# 464421_22-01_RF_Interface.net
KiCad netlist of a schematic drawn in Altium Designer
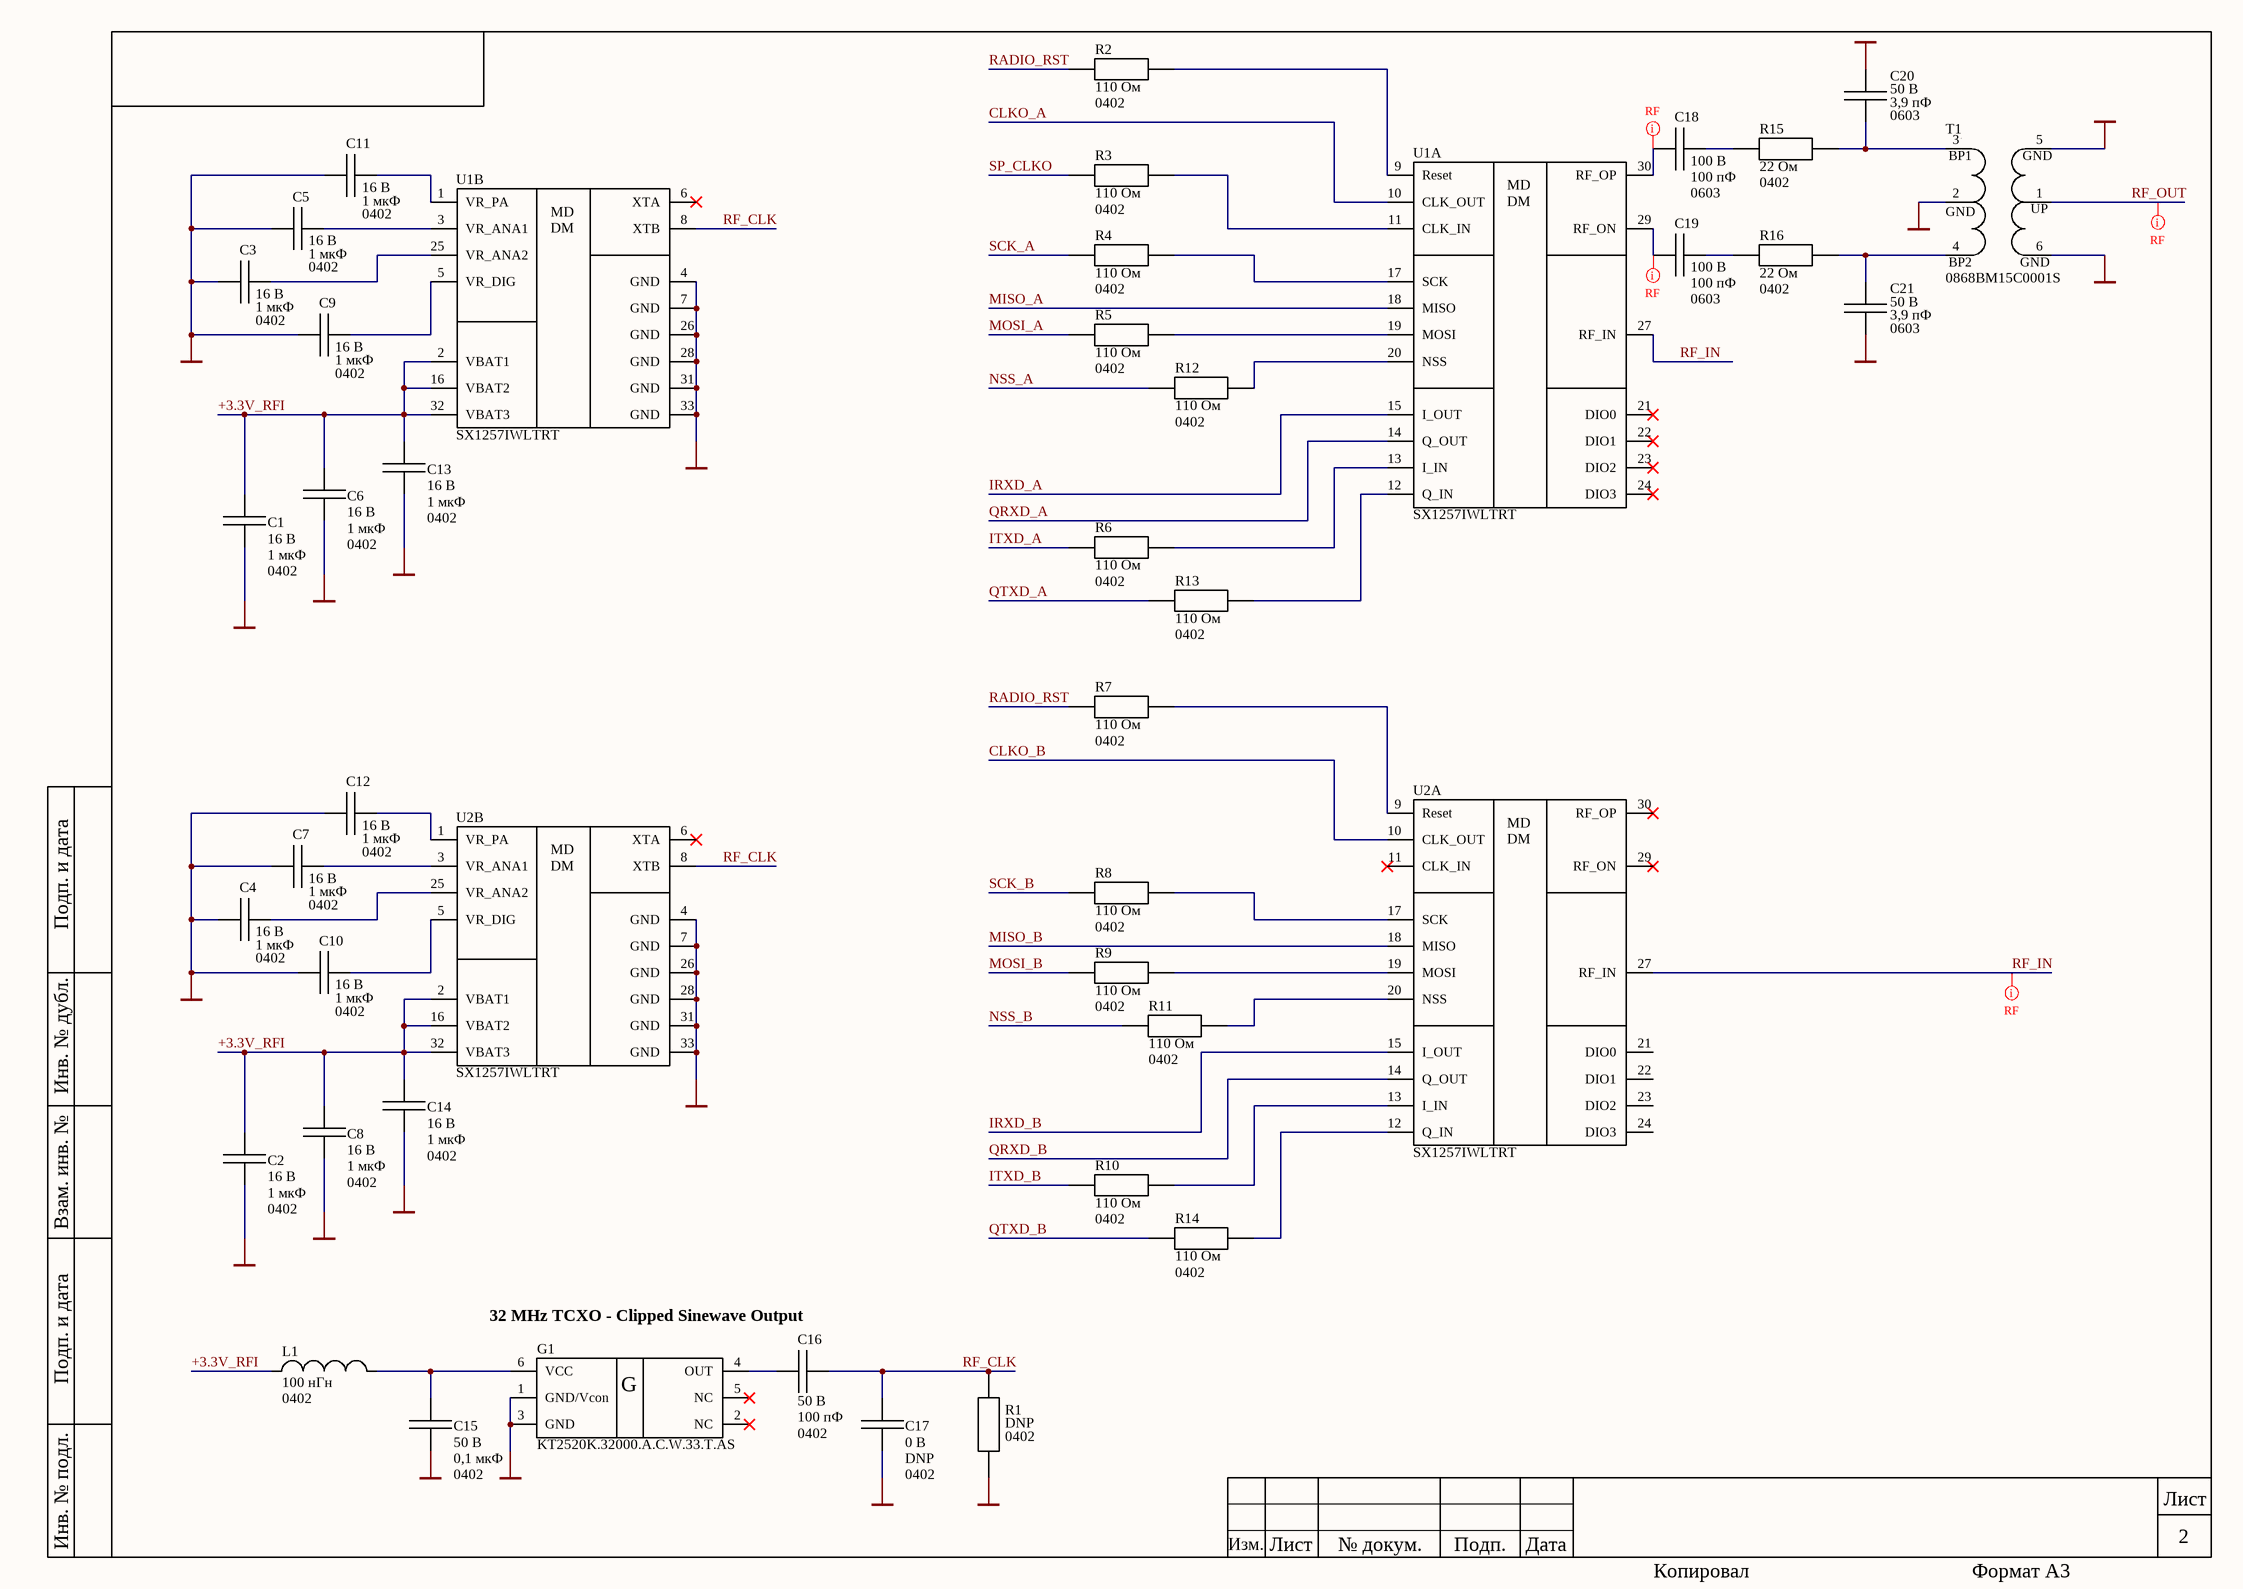
[diagram p0: МПСУ.464421.22-01 RF Interface.SchDoc]

(export (version "E")
  (design (tool "Eeschema 10.0.6"))
  (components
    (comp (ref "C1")
      (value "1 мкФ")
      (footprint "Passive_V2_0:CAPC100X50X55L20N")
      (description "Capacitor 0402")
      (fields
        (field (name "PARTNUMBER") "GRM155R61C105KA12D")
        (field (name "MANUFACTURER") "Murata")
        (field (name "PEAK_CONDITION") "16 В")
        (field (name "PACKAGE") "0402")
        (field (name "DESIGNER") "Свидерский")
      )
      (libsource (lib "Passive_V2_0") (part "C 0402"))
    )
    (comp (ref "C2")
      (value "1 мкФ")
      (footprint "Passive_V2_0:CAPC100X50X55L20N")
      (description "Capacitor 0402")
      (fields
        (field (name "PARTNUMBER") "GRM155R61C105KA12D")
        (field (name "MANUFACTURER") "Murata")
        (field (name "PEAK_CONDITION") "16 В")
        (field (name "PACKAGE") "0402")
        (field (name "DESIGNER") "Свидерский")
      )
      (libsource (lib "Passive_V2_0") (part "C 0402"))
    )
    (comp (ref "C3")
      (value "1 мкФ")
      (footprint "Passive_V2_0:CAPC100X50X55L20N")
      (description "Capacitor 0402")
      (fields
        (field (name "PARTNUMBER") "GRM155R61C105KA12D")
        (field (name "MANUFACTURER") "Murata")
        (field (name "PEAK_CONDITION") "16 В")
        (field (name "PACKAGE") "0402")
        (field (name "DESIGNER") "Свидерский")
      )
      (libsource (lib "Passive_V2_0") (part "C 0402"))
    )
    (comp (ref "C4")
      (value "1 мкФ")
      (footprint "Passive_V2_0:CAPC100X50X55L20N")
      (description "Capacitor 0402")
      (fields
        (field (name "PARTNUMBER") "GRM155R61C105KA12D")
        (field (name "MANUFACTURER") "Murata")
        (field (name "PEAK_CONDITION") "16 В")
        (field (name "PACKAGE") "0402")
        (field (name "DESIGNER") "Свидерский")
      )
      (libsource (lib "Passive_V2_0") (part "C 0402"))
    )
    (comp (ref "C5")
      (value "1 мкФ")
      (footprint "Passive_V2_0:CAPC100X50X55L20N")
      (description "Capacitor 0402")
      (fields
        (field (name "PARTNUMBER") "GRM155R61C105KA12D")
        (field (name "MANUFACTURER") "Murata")
        (field (name "PEAK_CONDITION") "16 В")
        (field (name "PACKAGE") "0402")
        (field (name "DESIGNER") "Свидерский")
      )
      (libsource (lib "Passive_V2_0") (part "C 0402"))
    )
    (comp (ref "C6")
      (value "1 мкФ")
      (footprint "Passive_V2_0:CAPC100X50X55L20N")
      (description "Capacitor 0402")
      (fields
        (field (name "PARTNUMBER") "GRM155R61C105KA12D")
        (field (name "MANUFACTURER") "Murata")
        (field (name "PEAK_CONDITION") "16 В")
        (field (name "PACKAGE") "0402")
        (field (name "DESIGNER") "Свидерский")
      )
      (libsource (lib "Passive_V2_0") (part "C 0402"))
    )
    (comp (ref "C7")
      (value "1 мкФ")
      (footprint "Passive_V2_0:CAPC100X50X55L20N")
      (description "Capacitor 0402")
      (fields
        (field (name "PARTNUMBER") "GRM155R61C105KA12D")
        (field (name "MANUFACTURER") "Murata")
        (field (name "PEAK_CONDITION") "16 В")
        (field (name "PACKAGE") "0402")
        (field (name "DESIGNER") "Свидерский")
      )
      (libsource (lib "Passive_V2_0") (part "C 0402"))
    )
    (comp (ref "C8")
      (value "1 мкФ")
      (footprint "Passive_V2_0:CAPC100X50X55L20N")
      (description "Capacitor 0402")
      (fields
        (field (name "PARTNUMBER") "GRM155R61C105KA12D")
        (field (name "MANUFACTURER") "Murata")
        (field (name "PEAK_CONDITION") "16 В")
        (field (name "PACKAGE") "0402")
        (field (name "DESIGNER") "Свидерский")
      )
      (libsource (lib "Passive_V2_0") (part "C 0402"))
    )
    (comp (ref "C9")
      (value "1 мкФ")
      (footprint "Passive_V2_0:CAPC100X50X55L20N")
      (description "Capacitor 0402")
      (fields
        (field (name "PARTNUMBER") "GRM155R61C105KA12D")
        (field (name "MANUFACTURER") "Murata")
        (field (name "PEAK_CONDITION") "16 В")
        (field (name "PACKAGE") "0402")
        (field (name "DESIGNER") "Свидерский")
      )
      (libsource (lib "Passive_V2_0") (part "C 0402"))
    )
    (comp (ref "C10")
      (value "1 мкФ")
      (footprint "Passive_V2_0:CAPC100X50X55L20N")
      (description "Capacitor 0402")
      (fields
        (field (name "PARTNUMBER") "GRM155R61C105KA12D")
        (field (name "MANUFACTURER") "Murata")
        (field (name "PEAK_CONDITION") "16 В")
        (field (name "PACKAGE") "0402")
        (field (name "DESIGNER") "Свидерский")
      )
      (libsource (lib "Passive_V2_0") (part "C 0402"))
    )
    (comp (ref "C11")
      (value "1 мкФ")
      (footprint "Passive_V2_0:CAPC100X50X55L20N")
      (description "Capacitor 0402")
      (fields
        (field (name "PARTNUMBER") "GRM155R61C105KA12D")
        (field (name "MANUFACTURER") "Murata")
        (field (name "PEAK_CONDITION") "16 В")
        (field (name "PACKAGE") "0402")
        (field (name "DESIGNER") "Свидерский")
      )
      (libsource (lib "Passive_V2_0") (part "C 0402"))
    )
    (comp (ref "C12")
      (value "1 мкФ")
      (footprint "Passive_V2_0:CAPC100X50X55L20N")
      (description "Capacitor 0402")
      (fields
        (field (name "PARTNUMBER") "GRM155R61C105KA12D")
        (field (name "MANUFACTURER") "Murata")
        (field (name "PEAK_CONDITION") "16 В")
        (field (name "PACKAGE") "0402")
        (field (name "DESIGNER") "Свидерский")
      )
      (libsource (lib "Passive_V2_0") (part "C 0402"))
    )
    (comp (ref "C13")
      (value "1 мкФ")
      (footprint "Passive_V2_0:CAPC100X50X55L20N")
      (description "Capacitor 0402")
      (fields
        (field (name "PARTNUMBER") "GRM155R61C105KA12D")
        (field (name "MANUFACTURER") "Murata")
        (field (name "PEAK_CONDITION") "16 В")
        (field (name "PACKAGE") "0402")
        (field (name "DESIGNER") "Свидерский")
      )
      (libsource (lib "Passive_V2_0") (part "C 0402"))
    )
    (comp (ref "C14")
      (value "1 мкФ")
      (footprint "Passive_V2_0:CAPC100X50X55L20N")
      (description "Capacitor 0402")
      (fields
        (field (name "PARTNUMBER") "GRM155R61C105KA12D")
        (field (name "MANUFACTURER") "Murata")
        (field (name "PEAK_CONDITION") "16 В")
        (field (name "PACKAGE") "0402")
        (field (name "DESIGNER") "Свидерский")
      )
      (libsource (lib "Passive_V2_0") (part "C 0402"))
    )
    (comp (ref "C15")
      (value "0,1 мкФ")
      (footprint "Passive_V2_0:CAPC100X50X55L20N")
      (description "Capacitor 0402")
      (fields
        (field (name "PARTNUMBER") "GRM155R71H104KE14J")
        (field (name "MANUFACTURER") "Murata")
        (field (name "PEAK_CONDITION") "50 В")
        (field (name "PACKAGE") "0402")
        (field (name "DESIGNER") "Свидерский")
      )
      (libsource (lib "Passive_V2_0") (part "C 0402"))
    )
    (comp (ref "C16")
      (value "100 пФ")
      (footprint "Passive_V2_0:CAPC100X50X55L20N")
      (description "Capacitor 0402")
      (fields
        (field (name "PARTNUMBER") "GRM1555C1H101JZ01D")
        (field (name "MANUFACTURER") "Murata")
        (field (name "PEAK_CONDITION") "50 В")
        (field (name "PACKAGE") "0402")
        (field (name "DESIGNER") "Свидерский")
      )
      (libsource (lib "Passive_V2_0") (part "C 0402"))
    )
    (comp (ref "C17")
      (value "DNP")
      (footprint "Passive_V2_0:CAPC100X50X55L20N")
      (description "Capacitor 0402")
      (fields
        (field (name "TOLERANCE") "0 %")
        (field (name "PEAK_CONDITION") "0 В")
        (field (name "PACKAGE") "0402")
        (field (name "Comment") "DNP 0402")
        (field (name "DESIGNER") "Свидерский")
      )
      (libsource (lib "Passive_V2_0") (part "C 0402"))
    )
    (comp (ref "C18")
      (value "100 пФ")
      (footprint "Passive_V2_0:CAPC160X80X90L30N")
      (description "Capacitor 0603")
      (fields
        (field (name "PARTNUMBER") "GRM1885C2A101FA01D")
        (field (name "MANUFACTURER") "Murata")
        (field (name "PEAK_CONDITION") "100 В")
        (field (name "PACKAGE") "0603")
        (field (name "DESIGNER") "Свидерский")
      )
      (libsource (lib "Passive_V2_0") (part "C 0603"))
    )
    (comp (ref "C19")
      (value "100 пФ")
      (footprint "Passive_V2_0:CAPC160X80X90L30N")
      (description "Capacitor 0603")
      (fields
        (field (name "PARTNUMBER") "GRM1885C2A101FA01D")
        (field (name "MANUFACTURER") "Murata")
        (field (name "PEAK_CONDITION") "100 В")
        (field (name "PACKAGE") "0603")
        (field (name "DESIGNER") "Свидерский")
      )
      (libsource (lib "Passive_V2_0") (part "C 0603"))
    )
    (comp (ref "C20")
      (value "3,9 пФ")
      (footprint "Passive_V2_0:CAPC160X80X90L30N")
      (description "Capacitor 0603")
      (fields
        (field (name "PARTNUMBER") "GRM1885C1H3R9CZ01D")
        (field (name "MANUFACTURER") "Murata")
        (field (name "PEAK_CONDITION") "50 В")
        (field (name "PACKAGE") "0603")
        (field (name "DESIGNER") "Свидерский")
      )
      (libsource (lib "Passive_V2_0") (part "C 0603"))
    )
    (comp (ref "C21")
      (value "3,9 пФ")
      (footprint "Passive_V2_0:CAPC160X80X90L30N")
      (description "Capacitor 0603")
      (fields
        (field (name "PARTNUMBER") "GRM1885C1H3R9CZ01D")
        (field (name "MANUFACTURER") "Murata")
        (field (name "PEAK_CONDITION") "50 В")
        (field (name "PACKAGE") "0603")
        (field (name "DESIGNER") "Свидерский")
      )
      (libsource (lib "Passive_V2_0") (part "C 0603"))
    )
    (comp (ref "G1")
      (value "KT2520K.32000.A.C.W.33.T.AS")
      (footprint "IC_V2_0:KT2520K")
      (description "Temperature Compensated Crystal Oscillators (TCXO, VCTCXO) Surface Mount Type")
      (fields
        (field (name "MANUFACTURER") "Kyocera")
        (field (name "PARTNUMBER") "KT2520K.32000.A.C.W.33.T.AS")
        (field (name "DESIGNER") "Лазба")
      )
      (libsource (lib "IC_V2_0") (part "KT2520K.*****.*.*.*.**.*.*"))
    )
    (comp (ref "L1")
      (value "100 нГн")
      (footprint "Passive_V2_0:INDC100X50X60L10N")
      (description "Inductor 0402")
      (fields
        (field (name "PARTNUMBER") "LQG15HNR10J02D")
        (field (name "TOLERANCE") "5 %")
        (field (name "PACKAGE") "0402")
        (field (name "DESIGNER") "Свидерский")
      )
      (libsource (lib "Passive_V2_0") (part "L 0402"))
    )
    (comp (ref "R1")
      (value "DNP")
      (footprint "Passive_V2_0:RESC100X50X40L25N")
      (description "Resistor 0402")
      (fields
        (field (name "TOLERANCE") "0 %")
        (field (name "PACKAGE") "0402")
        (field (name "Comment") "DNP 0402")
        (field (name "DESIGNER") "Свидерский")
      )
      (libsource (lib "") (part "R 0402_1"))
    )
    (comp (ref "R2")
      (value "110 Ом")
      (footprint "Passive_V2_0:RESC100X50X40L25N")
      (description "Resistor 0402")
      (fields
        (field (name "PARTNUMBER") "RC-02U111JT")
        (field (name "TOLERANCE") "5 %")
        (field (name "PACKAGE") "0402")
        (field (name "DESIGNER") "Свидерский")
      )
      (libsource (lib "Passive_V2_0") (part "R 0402"))
    )
    (comp (ref "R3")
      (value "110 Ом")
      (footprint "Passive_V2_0:RESC100X50X40L25N")
      (description "Resistor 0402")
      (fields
        (field (name "PARTNUMBER") "RC-02U111JT")
        (field (name "TOLERANCE") "5 %")
        (field (name "PACKAGE") "0402")
        (field (name "DESIGNER") "Свидерский")
      )
      (libsource (lib "Passive_V2_0") (part "R 0402"))
    )
    (comp (ref "R4")
      (value "110 Ом")
      (footprint "Passive_V2_0:RESC100X50X40L25N")
      (description "Resistor 0402")
      (fields
        (field (name "PARTNUMBER") "RC-02U111JT")
        (field (name "TOLERANCE") "5 %")
        (field (name "PACKAGE") "0402")
        (field (name "DESIGNER") "Свидерский")
      )
      (libsource (lib "Passive_V2_0") (part "R 0402"))
    )
    (comp (ref "R5")
      (value "110 Ом")
      (footprint "Passive_V2_0:RESC100X50X40L25N")
      (description "Resistor 0402")
      (fields
        (field (name "PARTNUMBER") "RC-02U111JT")
        (field (name "TOLERANCE") "5 %")
        (field (name "PACKAGE") "0402")
        (field (name "DESIGNER") "Свидерский")
      )
      (libsource (lib "Passive_V2_0") (part "R 0402"))
    )
    (comp (ref "R6")
      (value "110 Ом")
      (footprint "Passive_V2_0:RESC100X50X40L25N")
      (description "Resistor 0402")
      (fields
        (field (name "PARTNUMBER") "RC-02U111JT")
        (field (name "TOLERANCE") "5 %")
        (field (name "PACKAGE") "0402")
        (field (name "DESIGNER") "Свидерский")
      )
      (libsource (lib "Passive_V2_0") (part "R 0402"))
    )
    (comp (ref "R7")
      (value "110 Ом")
      (footprint "Passive_V2_0:RESC100X50X40L25N")
      (description "Resistor 0402")
      (fields
        (field (name "PARTNUMBER") "RC-02U111JT")
        (field (name "TOLERANCE") "5 %")
        (field (name "PACKAGE") "0402")
        (field (name "DESIGNER") "Свидерский")
      )
      (libsource (lib "Passive_V2_0") (part "R 0402"))
    )
    (comp (ref "R8")
      (value "110 Ом")
      (footprint "Passive_V2_0:RESC100X50X40L25N")
      (description "Resistor 0402")
      (fields
        (field (name "PARTNUMBER") "RC-02U111JT")
        (field (name "TOLERANCE") "5 %")
        (field (name "PACKAGE") "0402")
        (field (name "DESIGNER") "Свидерский")
      )
      (libsource (lib "Passive_V2_0") (part "R 0402"))
    )
    (comp (ref "R9")
      (value "110 Ом")
      (footprint "Passive_V2_0:RESC100X50X40L25N")
      (description "Resistor 0402")
      (fields
        (field (name "PARTNUMBER") "RC-02U111JT")
        (field (name "TOLERANCE") "5 %")
        (field (name "PACKAGE") "0402")
        (field (name "DESIGNER") "Свидерский")
      )
      (libsource (lib "Passive_V2_0") (part "R 0402"))
    )
    (comp (ref "R10")
      (value "110 Ом")
      (footprint "Passive_V2_0:RESC100X50X40L25N")
      (description "Resistor 0402")
      (fields
        (field (name "PARTNUMBER") "RC-02U111JT")
        (field (name "TOLERANCE") "5 %")
        (field (name "PACKAGE") "0402")
        (field (name "DESIGNER") "Свидерский")
      )
      (libsource (lib "Passive_V2_0") (part "R 0402"))
    )
    (comp (ref "R11")
      (value "110 Ом")
      (footprint "Passive_V2_0:RESC100X50X40L25N")
      (description "Resistor 0402")
      (fields
        (field (name "PARTNUMBER") "RC-02U111JT")
        (field (name "TOLERANCE") "5 %")
        (field (name "PACKAGE") "0402")
        (field (name "DESIGNER") "Свидерский")
      )
      (libsource (lib "Passive_V2_0") (part "R 0402"))
    )
    (comp (ref "R12")
      (value "110 Ом")
      (footprint "Passive_V2_0:RESC100X50X40L25N")
      (description "Resistor 0402")
      (fields
        (field (name "PARTNUMBER") "RC-02U111JT")
        (field (name "TOLERANCE") "5 %")
        (field (name "PACKAGE") "0402")
        (field (name "DESIGNER") "Свидерский")
      )
      (libsource (lib "Passive_V2_0") (part "R 0402"))
    )
    (comp (ref "R13")
      (value "110 Ом")
      (footprint "Passive_V2_0:RESC100X50X40L25N")
      (description "Resistor 0402")
      (fields
        (field (name "PARTNUMBER") "RC-02U111JT")
        (field (name "TOLERANCE") "5 %")
        (field (name "PACKAGE") "0402")
        (field (name "DESIGNER") "Свидерский")
      )
      (libsource (lib "Passive_V2_0") (part "R 0402"))
    )
    (comp (ref "R14")
      (value "110 Ом")
      (footprint "Passive_V2_0:RESC100X50X40L25N")
      (description "Resistor 0402")
      (fields
        (field (name "PARTNUMBER") "RC-02U111JT")
        (field (name "TOLERANCE") "5 %")
        (field (name "PACKAGE") "0402")
        (field (name "DESIGNER") "Свидерский")
      )
      (libsource (lib "Passive_V2_0") (part "R 0402"))
    )
    (comp (ref "R15")
      (value "22 Ом")
      (footprint "Passive_V2_0:RESC100X50X40L25N")
      (description "Resistor 0402")
      (fields
        (field (name "PARTNUMBER") "RC0402FR-0722RL")
        (field (name "TOLERANCE") "1 %")
        (field (name "PACKAGE") "0402")
        (field (name "DESIGNER") "Свидерский")
      )
      (libsource (lib "Passive_V2_0") (part "R 0402"))
    )
    (comp (ref "R16")
      (value "22 Ом")
      (footprint "Passive_V2_0:RESC100X50X40L25N")
      (description "Resistor 0402")
      (fields
        (field (name "PARTNUMBER") "RC0402FR-0722RL")
        (field (name "TOLERANCE") "1 %")
        (field (name "PACKAGE") "0402")
        (field (name "DESIGNER") "Свидерский")
      )
      (libsource (lib "Passive_V2_0") (part "R 0402"))
    )
    (comp (ref "T1")
      (value "0868BM15C0001S")
      (footprint "Passive_V2_0:LCC065P125X200X085-6")
      (fields
        (field (name "MANUFACTURER") "Johanson Technology Inc.")
        (field (name "PARTNUMBER") "0868BM15C0001S")
        (field (name "DESIGNER") "Лазба")
      )
      (libsource (lib "Passive_V2_0") (part "0868BM15C0001*"))
    )
    (comp (ref "U1")
      (value "SX1257IWLTRT")
      (footprint "IC_V2_0:SX1257IWLTRT")
      (description "LoRa Core™ Low Power Digital I and Q RF Multi-PHY Mode Analog Front End 860-1000MHz")
      (fields
        (field (name "MANUFACTURER") "Semtech")
        (field (name "PARTNUMBER") "SX1257IWLTRT")
        (field (name "DESIGNER") "Лазба")
      )
      (libsource (lib "IC_V2_0") (part "SX1257IWLTRT"))
    )
    (comp (ref "U2")
      (value "SX1257IWLTRT")
      (footprint "IC_V2_0:SX1257IWLTRT")
      (description "LoRa Core™ Low Power Digital I and Q RF Multi-PHY Mode Analog Front End 860-1000MHz")
      (fields
        (field (name "MANUFACTURER") "Semtech")
        (field (name "PARTNUMBER") "SX1257IWLTRT")
        (field (name "DESIGNER") "Лазба")
      )
      (libsource (lib "IC_V2_0") (part "SX1257IWLTRT"))
    )
  )
  (nets
    (net (code "1") (name "/+3.3V_RFI") (class "Default")
      (node (ref "C1") (pin "2") (pinfunction "2_2") (pintype "passive"))
      (node (ref "C13") (pin "2") (pinfunction "2_2") (pintype "passive"))
      (node (ref "C14") (pin "2") (pinfunction "2_2") (pintype "passive"))
      (node (ref "C2") (pin "2") (pinfunction "2_2") (pintype "passive"))
      (node (ref "C6") (pin "2") (pinfunction "2_2") (pintype "passive"))
      (node (ref "C8") (pin "2") (pinfunction "2_2") (pintype "passive"))
      (node (ref "L1") (pin "1") (pinfunction "1_1") (pintype "passive"))
      (node (ref "U1") (pin "16") (pinfunction "VBAT2_16") (pintype "passive"))
      (node (ref "U1") (pin "2") (pinfunction "VBAT1_2") (pintype "passive"))
      (node (ref "U1") (pin "32") (pinfunction "VBAT3_32") (pintype "passive"))
      (node (ref "U2") (pin "16") (pinfunction "VBAT2_16") (pintype "passive"))
      (node (ref "U2") (pin "2") (pinfunction "VBAT1_2") (pintype "passive"))
      (node (ref "U2") (pin "32") (pinfunction "VBAT3_32") (pintype "passive"))
    )
    (net (code "2") (name "/CLKO_A") (class "Default")
      (node (ref "U1") (pin "10") (pinfunction "CLK_OUT_10") (pintype "passive"))
    )
    (net (code "3") (name "/CLKO_B") (class "Default")
      (node (ref "U2") (pin "10") (pinfunction "CLK_OUT_10") (pintype "passive"))
    )
    (net (code "4") (name "/IRXD_A") (class "Default")
      (node (ref "U1") (pin "15") (pinfunction "I_OUT_15") (pintype "passive"))
    )
    (net (code "5") (name "/IRXD_B") (class "Default")
      (node (ref "U2") (pin "15") (pinfunction "I_OUT_15") (pintype "passive"))
    )
    (net (code "6") (name "/ITXD_A") (class "Default")
      (node (ref "R6") (pin "1") (pinfunction "1_1") (pintype "passive"))
    )
    (net (code "7") (name "/ITXD_B") (class "Default")
      (node (ref "R10") (pin "1") (pinfunction "1_1") (pintype "passive"))
    )
    (net (code "8") (name "/MISO_A") (class "Default")
      (node (ref "U1") (pin "18") (pinfunction "MISO_18") (pintype "passive"))
    )
    (net (code "9") (name "/MISO_B") (class "Default")
      (node (ref "U2") (pin "18") (pinfunction "MISO_18") (pintype "passive"))
    )
    (net (code "10") (name "/MOSI_A") (class "Default")
      (node (ref "R5") (pin "1") (pinfunction "1_1") (pintype "passive"))
    )
    (net (code "11") (name "/MOSI_B") (class "Default")
      (node (ref "R9") (pin "1") (pinfunction "1_1") (pintype "passive"))
    )
    (net (code "12") (name "/NSS_A") (class "Default")
      (node (ref "R12") (pin "1") (pinfunction "1_1") (pintype "passive"))
    )
    (net (code "13") (name "/NSS_B") (class "Default")
      (node (ref "R11") (pin "1") (pinfunction "1_1") (pintype "passive"))
    )
    (net (code "14") (name "/QRXD_A") (class "Default")
      (node (ref "U1") (pin "14") (pinfunction "Q_OUT_14") (pintype "passive"))
    )
    (net (code "15") (name "/QRXD_B") (class "Default")
      (node (ref "U2") (pin "14") (pinfunction "Q_OUT_14") (pintype "passive"))
    )
    (net (code "16") (name "/QTXD_A") (class "Default")
      (node (ref "R13") (pin "1") (pinfunction "1_1") (pintype "passive"))
    )
    (net (code "17") (name "/QTXD_B") (class "Default")
      (node (ref "R14") (pin "1") (pinfunction "1_1") (pintype "passive"))
    )
    (net (code "18") (name "/RADIO_RST") (class "Default")
      (node (ref "R2") (pin "1") (pinfunction "1_1") (pintype "passive"))
      (node (ref "R7") (pin "1") (pinfunction "1_1") (pintype "passive"))
    )
    (net (code "19") (name "/RF_CLK") (class "Default")
      (node (ref "C16") (pin "2") (pinfunction "2_2") (pintype "passive"))
      (node (ref "C17") (pin "1") (pinfunction "1_1") (pintype "passive"))
      (node (ref "R1") (pin "1") (pinfunction "1_1") (pintype "passive"))
      (node (ref "U1") (pin "8") (pinfunction "XTB_8") (pintype "passive"))
      (node (ref "U2") (pin "8") (pinfunction "XTB_8") (pintype "passive"))
    )
    (net (code "20") (name "/RF_IN") (class "Default")
      (node (ref "U1") (pin "27") (pinfunction "RF_IN_27") (pintype "passive"))
      (node (ref "U2") (pin "27") (pinfunction "RF_IN_27") (pintype "passive"))
    )
    (net (code "21") (name "/RF_OUT") (class "Default")
      (node (ref "T1") (pin "1") (pinfunction "UP_1") (pintype "passive"))
    )
    (net (code "22") (name "/SCK_A") (class "Default")
      (node (ref "R4") (pin "1") (pinfunction "1_1") (pintype "passive"))
    )
    (net (code "23") (name "/SCK_B") (class "Default")
      (node (ref "R8") (pin "1") (pinfunction "1_1") (pintype "passive"))
    )
    (net (code "24") (name "/SP_CLKO") (class "Default")
      (node (ref "R3") (pin "1") (pinfunction "1_1") (pintype "passive"))
    )
    (net (code "25") (name "GND") (class "Default")
      (node (ref "C1") (pin "1") (pinfunction "1_1") (pintype "passive"))
      (node (ref "C10") (pin "2") (pinfunction "2_2") (pintype "passive"))
      (node (ref "C11") (pin "2") (pinfunction "2_2") (pintype "passive"))
      (node (ref "C12") (pin "2") (pinfunction "2_2") (pintype "passive"))
      (node (ref "C13") (pin "1") (pinfunction "1_1") (pintype "passive"))
      (node (ref "C14") (pin "1") (pinfunction "1_1") (pintype "passive"))
      (node (ref "C15") (pin "2") (pinfunction "2_2") (pintype "passive"))
      (node (ref "C17") (pin "2") (pinfunction "2_2") (pintype "passive"))
      (node (ref "C2") (pin "1") (pinfunction "1_1") (pintype "passive"))
      (node (ref "C20") (pin "1") (pinfunction "1_1") (pintype "passive"))
      (node (ref "C21") (pin "2") (pinfunction "2_2") (pintype "passive"))
      (node (ref "C3") (pin "2") (pinfunction "2_2") (pintype "passive"))
      (node (ref "C4") (pin "2") (pinfunction "2_2") (pintype "passive"))
      (node (ref "C5") (pin "2") (pinfunction "2_2") (pintype "passive"))
      (node (ref "C6") (pin "1") (pinfunction "1_1") (pintype "passive"))
      (node (ref "C7") (pin "2") (pinfunction "2_2") (pintype "passive"))
      (node (ref "C8") (pin "1") (pinfunction "1_1") (pintype "passive"))
      (node (ref "C9") (pin "2") (pinfunction "2_2") (pintype "passive"))
      (node (ref "G1") (pin "1") (pinfunction "GND/Vcon_1") (pintype "passive"))
      (node (ref "G1") (pin "3") (pinfunction "GND_3") (pintype "passive"))
      (node (ref "R1") (pin "2") (pinfunction "2_2") (pintype "passive"))
      (node (ref "T1") (pin "2") (pinfunction "GND_2") (pintype "passive"))
      (node (ref "T1") (pin "5") (pinfunction "GND_5") (pintype "passive"))
      (node (ref "T1") (pin "6") (pinfunction "GND_6") (pintype "passive"))
      (node (ref "U1") (pin "26") (pinfunction "GND_26") (pintype "passive"))
      (node (ref "U1") (pin "28") (pinfunction "GND_28") (pintype "passive"))
      (node (ref "U1") (pin "31") (pinfunction "GND_31") (pintype "passive"))
      (node (ref "U1") (pin "33") (pinfunction "GND_33") (pintype "passive"))
      (node (ref "U1") (pin "4") (pinfunction "GND_4") (pintype "passive"))
      (node (ref "U1") (pin "7") (pinfunction "GND_7") (pintype "passive"))
      (node (ref "U2") (pin "26") (pinfunction "GND_26") (pintype "passive"))
      (node (ref "U2") (pin "28") (pinfunction "GND_28") (pintype "passive"))
      (node (ref "U2") (pin "31") (pinfunction "GND_31") (pintype "passive"))
      (node (ref "U2") (pin "33") (pinfunction "GND_33") (pintype "passive"))
      (node (ref "U2") (pin "4") (pinfunction "GND_4") (pintype "passive"))
      (node (ref "U2") (pin "7") (pinfunction "GND_7") (pintype "passive"))
    )
    (net (code "26") (name "Net-(C18-Pad2)") (class "Default")
      (node (ref "C18") (pin "2") (pinfunction "2_2") (pintype "passive"))
      (node (ref "R15") (pin "1") (pinfunction "1_1") (pintype "passive"))
    )
    (net (code "27") (name "Net-(C19-Pad2)") (class "Default")
      (node (ref "C19") (pin "2") (pinfunction "2_2") (pintype "passive"))
      (node (ref "R16") (pin "1") (pinfunction "1_1") (pintype "passive"))
    )
    (net (code "28") (name "Net-(G1-OUT)") (class "Default")
      (node (ref "C16") (pin "1") (pinfunction "1_1") (pintype "passive"))
      (node (ref "G1") (pin "4") (pinfunction "OUT_4") (pintype "passive"))
    )
    (net (code "29") (name "Net-(G1-VCC)") (class "Default")
      (node (ref "C15") (pin "1") (pinfunction "1_1") (pintype "passive"))
      (node (ref "G1") (pin "6") (pinfunction "VCC_6") (pintype "passive"))
      (node (ref "L1") (pin "2") (pinfunction "2_2") (pintype "passive"))
    )
    (net (code "30") (name "Net-(T1-BP1)") (class "Default")
      (node (ref "C20") (pin "2") (pinfunction "2_2") (pintype "passive"))
      (node (ref "R15") (pin "2") (pinfunction "2_2") (pintype "passive"))
      (node (ref "T1") (pin "3") (pinfunction "BP1_3") (pintype "passive"))
    )
    (net (code "31") (name "Net-(T1-BP2)") (class "Default")
      (node (ref "C21") (pin "1") (pinfunction "1_1") (pintype "passive"))
      (node (ref "R16") (pin "2") (pinfunction "2_2") (pintype "passive"))
      (node (ref "T1") (pin "4") (pinfunction "BP2_4") (pintype "passive"))
    )
    (net (code "32") (name "Net-(U1A-CLK_IN)") (class "Default")
      (node (ref "R3") (pin "2") (pinfunction "2_2") (pintype "passive"))
      (node (ref "U1") (pin "11") (pinfunction "CLK_IN_11") (pintype "passive"))
    )
    (net (code "33") (name "Net-(U1A-I_IN)") (class "Default")
      (node (ref "R6") (pin "2") (pinfunction "2_2") (pintype "passive"))
      (node (ref "U1") (pin "13") (pinfunction "I_IN_13") (pintype "passive"))
    )
    (net (code "34") (name "Net-(U1A-MOSI)") (class "Default")
      (node (ref "R5") (pin "2") (pinfunction "2_2") (pintype "passive"))
      (node (ref "U1") (pin "19") (pinfunction "MOSI_19") (pintype "passive"))
    )
    (net (code "35") (name "Net-(U1A-NSS)") (class "Default")
      (node (ref "R12") (pin "2") (pinfunction "2_2") (pintype "passive"))
      (node (ref "U1") (pin "20") (pinfunction "NSS_20") (pintype "passive"))
    )
    (net (code "36") (name "Net-(U1A-Q_IN)") (class "Default")
      (node (ref "R13") (pin "2") (pinfunction "2_2") (pintype "passive"))
      (node (ref "U1") (pin "12") (pinfunction "Q_IN_12") (pintype "passive"))
    )
    (net (code "37") (name "Net-(U1A-RF_ON)") (class "Default")
      (node (ref "C19") (pin "1") (pinfunction "1_1") (pintype "passive"))
      (node (ref "U1") (pin "29") (pinfunction "RF_ON_29") (pintype "passive"))
    )
    (net (code "38") (name "Net-(U1A-RF_OP)") (class "Default")
      (node (ref "C18") (pin "1") (pinfunction "1_1") (pintype "passive"))
      (node (ref "U1") (pin "30") (pinfunction "RF_OP_30") (pintype "passive"))
    )
    (net (code "39") (name "Net-(U1A-Reset)") (class "Default")
      (node (ref "R2") (pin "2") (pinfunction "2_2") (pintype "passive"))
      (node (ref "U1") (pin "9") (pinfunction "Reset_9") (pintype "passive"))
    )
    (net (code "40") (name "Net-(U1A-SCK)") (class "Default")
      (node (ref "R4") (pin "2") (pinfunction "2_2") (pintype "passive"))
      (node (ref "U1") (pin "17") (pinfunction "SCK_17") (pintype "passive"))
    )
    (net (code "41") (name "Net-(U1B-VR_ANA1)") (class "Default")
      (node (ref "C5") (pin "1") (pinfunction "1_1") (pintype "passive"))
      (node (ref "U1") (pin "3") (pinfunction "VR_ANA1_3") (pintype "passive"))
    )
    (net (code "42") (name "Net-(U1B-VR_ANA2)") (class "Default")
      (node (ref "C3") (pin "1") (pinfunction "1_1") (pintype "passive"))
      (node (ref "U1") (pin "25") (pinfunction "VR_ANA2_25") (pintype "passive"))
    )
    (net (code "43") (name "Net-(U1B-VR_DIG)") (class "Default")
      (node (ref "C9") (pin "1") (pinfunction "1_1") (pintype "passive"))
      (node (ref "U1") (pin "5") (pinfunction "VR_DIG_5") (pintype "passive"))
    )
    (net (code "44") (name "Net-(U1B-VR_PA)") (class "Default")
      (node (ref "C11") (pin "1") (pinfunction "1_1") (pintype "passive"))
      (node (ref "U1") (pin "1") (pinfunction "VR_PA_1") (pintype "passive"))
    )
    (net (code "45") (name "Net-(U2A-I_IN)") (class "Default")
      (node (ref "R10") (pin "2") (pinfunction "2_2") (pintype "passive"))
      (node (ref "U2") (pin "13") (pinfunction "I_IN_13") (pintype "passive"))
    )
    (net (code "46") (name "Net-(U2A-MOSI)") (class "Default")
      (node (ref "R9") (pin "2") (pinfunction "2_2") (pintype "passive"))
      (node (ref "U2") (pin "19") (pinfunction "MOSI_19") (pintype "passive"))
    )
    (net (code "47") (name "Net-(U2A-NSS)") (class "Default")
      (node (ref "R11") (pin "2") (pinfunction "2_2") (pintype "passive"))
      (node (ref "U2") (pin "20") (pinfunction "NSS_20") (pintype "passive"))
    )
    (net (code "48") (name "Net-(U2A-Q_IN)") (class "Default")
      (node (ref "R14") (pin "2") (pinfunction "2_2") (pintype "passive"))
      (node (ref "U2") (pin "12") (pinfunction "Q_IN_12") (pintype "passive"))
    )
    (net (code "49") (name "Net-(U2A-Reset)") (class "Default")
      (node (ref "R7") (pin "2") (pinfunction "2_2") (pintype "passive"))
      (node (ref "U2") (pin "9") (pinfunction "Reset_9") (pintype "passive"))
    )
    (net (code "50") (name "Net-(U2A-SCK)") (class "Default")
      (node (ref "R8") (pin "2") (pinfunction "2_2") (pintype "passive"))
      (node (ref "U2") (pin "17") (pinfunction "SCK_17") (pintype "passive"))
    )
    (net (code "51") (name "Net-(U2B-VR_ANA1)") (class "Default")
      (node (ref "C7") (pin "1") (pinfunction "1_1") (pintype "passive"))
      (node (ref "U2") (pin "3") (pinfunction "VR_ANA1_3") (pintype "passive"))
    )
    (net (code "52") (name "Net-(U2B-VR_ANA2)") (class "Default")
      (node (ref "C4") (pin "1") (pinfunction "1_1") (pintype "passive"))
      (node (ref "U2") (pin "25") (pinfunction "VR_ANA2_25") (pintype "passive"))
    )
    (net (code "53") (name "Net-(U2B-VR_DIG)") (class "Default")
      (node (ref "C10") (pin "1") (pinfunction "1_1") (pintype "passive"))
      (node (ref "U2") (pin "5") (pinfunction "VR_DIG_5") (pintype "passive"))
    )
    (net (code "54") (name "Net-(U2B-VR_PA)") (class "Default")
      (node (ref "C12") (pin "1") (pinfunction "1_1") (pintype "passive"))
      (node (ref "U2") (pin "1") (pinfunction "VR_PA_1") (pintype "passive"))
    )
    (net (code "55") (name "unconnected-(G1-NC-Pad2)") (class "Default")
      (node (ref "G1") (pin "2") (pinfunction "NC_2") (pintype "passive+no_connect"))
    )
    (net (code "56") (name "unconnected-(G1-NC-Pad5)") (class "Default")
      (node (ref "G1") (pin "5") (pinfunction "NC_5") (pintype "passive+no_connect"))
    )
    (net (code "57") (name "unconnected-(U1A-DIO0-Pad21)") (class "Default")
      (node (ref "U1") (pin "21") (pinfunction "DIO0_21") (pintype "passive+no_connect"))
    )
    (net (code "58") (name "unconnected-(U1A-DIO1-Pad22)") (class "Default")
      (node (ref "U1") (pin "22") (pinfunction "DIO1_22") (pintype "passive+no_connect"))
    )
    (net (code "59") (name "unconnected-(U1A-DIO2-Pad23)") (class "Default")
      (node (ref "U1") (pin "23") (pinfunction "DIO2_23") (pintype "passive+no_connect"))
    )
    (net (code "60") (name "unconnected-(U1A-DIO3-Pad24)") (class "Default")
      (node (ref "U1") (pin "24") (pinfunction "DIO3_24") (pintype "passive+no_connect"))
    )
    (net (code "61") (name "unconnected-(U1B-XTA-Pad6)") (class "Default")
      (node (ref "U1") (pin "6") (pinfunction "XTA_6") (pintype "passive+no_connect"))
    )
    (net (code "62") (name "unconnected-(U2A-CLK_IN-Pad11)") (class "Default")
      (node (ref "U2") (pin "11") (pinfunction "CLK_IN_11") (pintype "passive+no_connect"))
    )
    (net (code "63") (name "unconnected-(U2A-DIO0-Pad21)") (class "Default")
      (node (ref "U2") (pin "21") (pinfunction "DIO0_21") (pintype "passive"))
    )
    (net (code "64") (name "unconnected-(U2A-DIO1-Pad22)") (class "Default")
      (node (ref "U2") (pin "22") (pinfunction "DIO1_22") (pintype "passive"))
    )
    (net (code "65") (name "unconnected-(U2A-DIO2-Pad23)") (class "Default")
      (node (ref "U2") (pin "23") (pinfunction "DIO2_23") (pintype "passive"))
    )
    (net (code "66") (name "unconnected-(U2A-DIO3-Pad24)") (class "Default")
      (node (ref "U2") (pin "24") (pinfunction "DIO3_24") (pintype "passive"))
    )
    (net (code "67") (name "unconnected-(U2A-RF_ON-Pad29)") (class "Default")
      (node (ref "U2") (pin "29") (pinfunction "RF_ON_29") (pintype "passive+no_connect"))
    )
    (net (code "68") (name "unconnected-(U2A-RF_OP-Pad30)") (class "Default")
      (node (ref "U2") (pin "30") (pinfunction "RF_OP_30") (pintype "passive+no_connect"))
    )
    (net (code "69") (name "unconnected-(U2B-XTA-Pad6)") (class "Default")
      (node (ref "U2") (pin "6") (pinfunction "XTA_6") (pintype "passive+no_connect"))
    )
  )
)
